# interface_dac_sma_feedback_2PS_ADC_detec.net
KiCad netlist of a schematic drawn in EAGLE
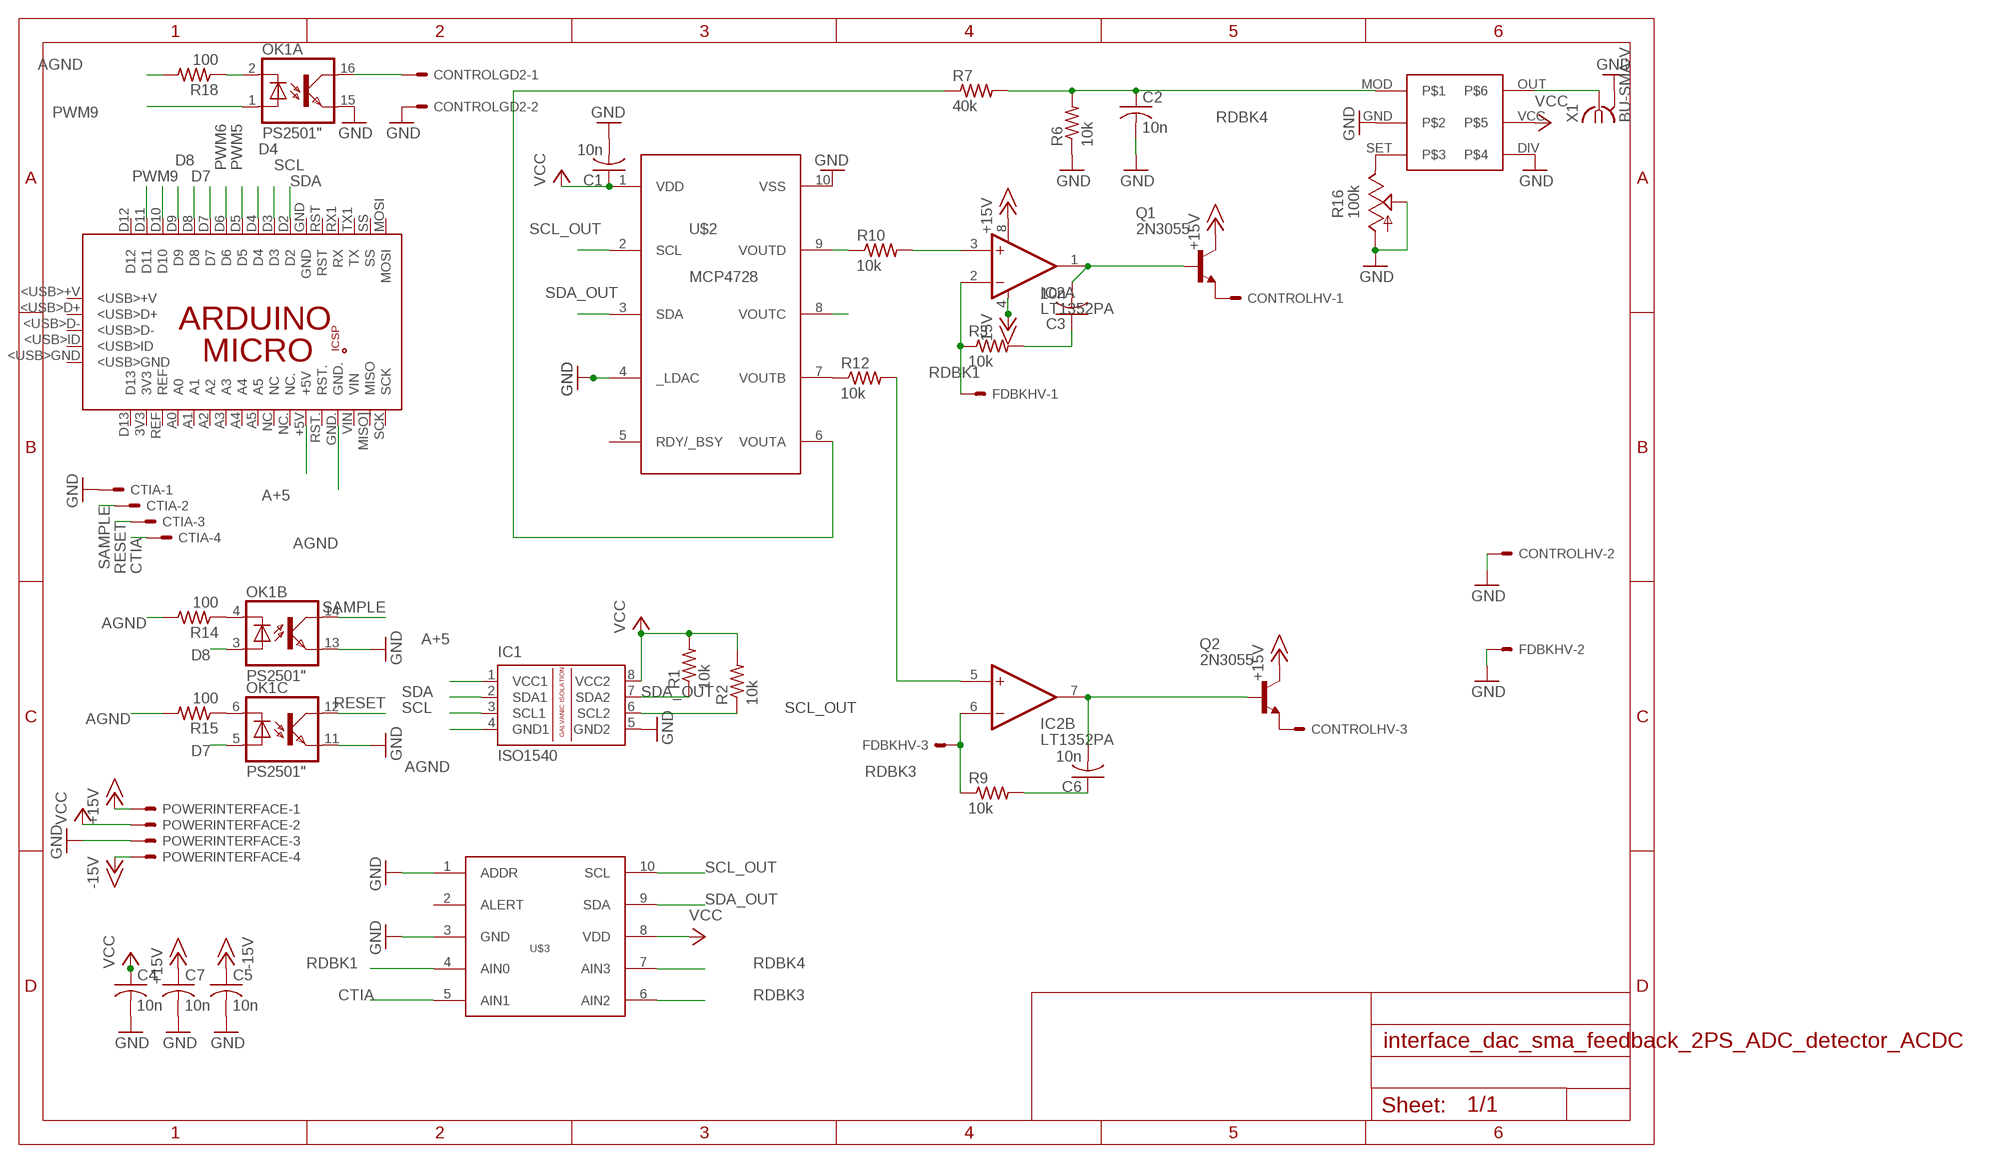
[diagram p0: schematic, sheet 1]

(export (version "E")
  (design (tool "Eeschema 10.0.6"))
  (components
    (comp (ref "C1")
      (value "10n")
      (footprint "eagle-import:C050-024X044")
      (libsource (lib "eagle-import") (part "C-US050-024X044"))
    )
    (comp (ref "C2")
      (value "10n")
      (footprint "eagle-import:C050-024X044")
      (libsource (lib "eagle-import") (part "resistor_C-US050-024X044"))
    )
    (comp (ref "C3")
      (value "10n")
      (footprint "eagle-import:C050-024X044")
      (libsource (lib "eagle-import") (part "resistor_C-US050-024X044"))
    )
    (comp (ref "C4")
      (value "10n")
      (footprint "eagle-import:C050-024X044")
      (libsource (lib "eagle-import") (part "resistor_C-US050-024X044"))
    )
    (comp (ref "C5")
      (value "10n")
      (footprint "eagle-import:C050-024X044")
      (libsource (lib "eagle-import") (part "resistor_C-US050-024X044"))
    )
    (comp (ref "C6")
      (value "10n")
      (footprint "eagle-import:C050-024X044")
      (libsource (lib "eagle-import") (part "resistor_C-US050-024X044"))
    )
    (comp (ref "C7")
      (value "10n")
      (footprint "eagle-import:C050-024X044")
      (libsource (lib "eagle-import") (part "resistor_C-US050-024X044"))
    )
    (comp (ref "CONTROLGD2")
      (value "KK-156-2")
      (footprint "eagle-import:KK-156-2")
      (libsource (lib "eagle-import") (part "KK-156-2"))
    )
    (comp (ref "CONTROLHV")
      (value "KK-156-3")
      (footprint "eagle-import:KK-156-3")
      (libsource (lib "eagle-import") (part "KK-156-3"))
    )
    (comp (ref "CTIA")
      (value "KK-156-4")
      (footprint "eagle-import:KK-156-4")
      (libsource (lib "eagle-import") (part "KK-156-4"))
    )
    (comp (ref "FDBKHV")
      (value "KK-156-3")
      (footprint "eagle-import:KK-156-3")
      (libsource (lib "eagle-import") (part "KK-156-3"))
    )
    (comp (ref "IC1")
      (value "ISO1540")
      (footprint "eagle-import:DIL08")
      (libsource (lib "eagle-import") (part "ISO1540"))
    )
    (comp (ref "IC2")
      (value "LT1352PA")
      (footprint "eagle-import:DIL08")
      (libsource (lib "eagle-import") (part "LT1352PA"))
    )
    (comp (ref "OK1")
      (value "PS2501\"")
      (footprint "eagle-import:DIL16")
      (libsource (lib "eagle-import") (part "PS2501{dblquote}"))
    )
    (comp (ref "PCB1")
      (value "ARDUINO_MICRO")
      (footprint "eagle-import:ARDUINO_MICRO")
      (libsource (lib "eagle-import") (part "ARDUINO_MICRO"))
    )
    (comp (ref "POWERINTERFACE")
      (value "KK-156-4")
      (footprint "eagle-import:KK-156-4")
      (libsource (lib "eagle-import") (part "KK-156-4"))
    )
    (comp (ref "Q1")
      (value "2N3055")
      (footprint "eagle-import:TO3")
      (libsource (lib "eagle-import") (part "2N3055"))
    )
    (comp (ref "Q2")
      (value "2N3055")
      (footprint "eagle-import:TO3")
      (libsource (lib "eagle-import") (part "2N3055"))
    )
    (comp (ref "R1")
      (value "10k")
      (footprint "eagle-import:0207_12")
      (libsource (lib "eagle-import") (part "resistor_R-US_0207/12"))
    )
    (comp (ref "R2")
      (value "10k")
      (footprint "eagle-import:0207_10")
      (libsource (lib "eagle-import") (part "resistor_R-US_0207/10"))
    )
    (comp (ref "R3")
      (value "10k")
      (footprint "eagle-import:0207_10")
      (libsource (lib "eagle-import") (part "resistor_R-US_0207/10"))
    )
    (comp (ref "R6")
      (value "10k")
      (footprint "eagle-import:0207_10")
      (libsource (lib "eagle-import") (part "resistor_R-US_0207/10"))
    )
    (comp (ref "R7")
      (value "40k")
      (footprint "eagle-import:0207_10")
      (libsource (lib "eagle-import") (part "resistor_R-US_0207/10"))
    )
    (comp (ref "R9")
      (value "10k")
      (footprint "eagle-import:0207_10")
      (libsource (lib "eagle-import") (part "resistor_R-US_0207/10"))
    )
    (comp (ref "R10")
      (value "10k")
      (footprint "eagle-import:0207_10")
      (libsource (lib "eagle-import") (part "resistor_R-US_0207/10"))
    )
    (comp (ref "R12")
      (value "10k")
      (footprint "eagle-import:0207_10")
      (libsource (lib "eagle-import") (part "resistor_R-US_0207/10"))
    )
    (comp (ref "R14")
      (value "100")
      (footprint "eagle-import:0207_10")
      (libsource (lib "eagle-import") (part "R-US_0207/10"))
    )
    (comp (ref "R15")
      (value "100")
      (footprint "eagle-import:0207_10")
      (libsource (lib "eagle-import") (part "R-US_0207/10"))
    )
    (comp (ref "R16")
      (value "100k")
      (footprint "eagle-import:SP19L")
      (libsource (lib "eagle-import") (part "TRIM_US-B90P"))
    )
    (comp (ref "R18")
      (value "100")
      (footprint "eagle-import:0207_10")
      (libsource (lib "eagle-import") (part "R-US_0207/10"))
    )
    (comp (ref "U$1")
      (value "LTC6992")
      (footprint "eagle-import:DIL06")
      (libsource (lib "eagle-import") (part "LTC6992"))
    )
    (comp (ref "U$2")
      (value "MCP4728DIL")
      (footprint "eagle-import:DIL10")
      (libsource (lib "eagle-import") (part "MCP4728DIL"))
    )
    (comp (ref "U$3")
      (value "ADS1015DIL")
      (footprint "eagle-import:DIL10")
      (libsource (lib "eagle-import") (part "ADS1015DIL"))
    )
    (comp (ref "X1")
      (value "BU-SMA-V")
      (footprint "eagle-import:BU-SMA-V")
      (libsource (lib "eagle-import") (part "BU-SMA-V"))
    )
  )
  (nets
    (net (code "1") (name "+15V") (class "Default")
      (node (ref "C7") (pin "1") (pinfunction "1_1") (pintype "passive"))
      (node (ref "IC2") (pin "8") (pinfunction "V+_8") (pintype "power_in"))
      (node (ref "POWERINTERFACE") (pin "1") (pinfunction "S_1") (pintype "passive"))
      (node (ref "Q1") (pin "C") (pinfunction "C_C") (pintype "passive"))
      (node (ref "Q1") (pin "C/") (pinfunction "C_C/") (pintype "passive"))
      (node (ref "Q2") (pin "C") (pinfunction "C_C") (pintype "passive"))
      (node (ref "Q2") (pin "C/") (pinfunction "C_C/") (pintype "passive"))
    )
    (net (code "2") (name "-15V") (class "Default")
      (node (ref "C5") (pin "1") (pinfunction "1_1") (pintype "passive"))
      (node (ref "IC2") (pin "4") (pinfunction "V-_4") (pintype "power_in"))
      (node (ref "POWERINTERFACE") (pin "4") (pinfunction "S_4") (pintype "passive"))
    )
    (net (code "3") (name "/A+5") (class "Default")
      (node (ref "IC1") (pin "1") (pinfunction "VCC1_1") (pintype "input"))
      (node (ref "PCB1") (pin "+5V") (pinfunction "+5V_+5V") (pintype "bidirectional"))
    )
    (net (code "4") (name "/AGND") (class "Default")
      (node (ref "IC1") (pin "4") (pinfunction "GND1_4") (pintype "input"))
      (node (ref "PCB1") (pin "GND.") (pinfunction "GND._GND.") (pintype "bidirectional"))
      (node (ref "R14") (pin "2") (pinfunction "2_2") (pintype "passive"))
      (node (ref "R15") (pin "2") (pinfunction "2_2") (pintype "passive"))
      (node (ref "R18") (pin "2") (pinfunction "2_2") (pintype "passive"))
    )
    (net (code "5") (name "/CTIA") (class "Default")
      (node (ref "CTIA") (pin "4") (pinfunction "S_4") (pintype "passive"))
      (node (ref "U$3") (pin "5") (pinfunction "AIN1_5") (pintype "bidirectional"))
    )
    (net (code "6") (name "/D4") (class "Default")
      (node (ref "PCB1") (pin "D4") (pinfunction "D4_D4") (pintype "bidirectional"))
    )
    (net (code "7") (name "/D7") (class "Default")
      (node (ref "OK1") (pin "5") (pinfunction "A_5") (pintype "passive"))
      (node (ref "PCB1") (pin "D7") (pinfunction "D7_D7") (pintype "bidirectional"))
    )
    (net (code "8") (name "/D8") (class "Default")
      (node (ref "OK1") (pin "3") (pinfunction "A_3") (pintype "passive"))
      (node (ref "PCB1") (pin "D8") (pinfunction "D8_D8") (pintype "bidirectional"))
    )
    (net (code "9") (name "/PWM5") (class "Default")
      (node (ref "PCB1") (pin "D5") (pinfunction "D5_D5") (pintype "bidirectional"))
    )
    (net (code "10") (name "/PWM6") (class "Default")
      (node (ref "PCB1") (pin "D6") (pinfunction "D6_D6") (pintype "bidirectional"))
    )
    (net (code "11") (name "/PWM9") (class "Default")
      (node (ref "OK1") (pin "1") (pinfunction "A_1") (pintype "passive"))
      (node (ref "PCB1") (pin "D9") (pinfunction "D9_D9") (pintype "bidirectional"))
    )
    (net (code "12") (name "/RDBK1") (class "Default")
      (node (ref "FDBKHV") (pin "1") (pinfunction "S_1") (pintype "passive"))
      (node (ref "IC2") (pin "2") (pinfunction "-IN_2") (pintype "input"))
      (node (ref "R3") (pin "1") (pinfunction "1_1") (pintype "passive"))
      (node (ref "U$3") (pin "4") (pinfunction "AIN0_4") (pintype "bidirectional"))
    )
    (net (code "13") (name "/RDBK3") (class "Default")
      (node (ref "FDBKHV") (pin "3") (pinfunction "S_3") (pintype "passive"))
      (node (ref "IC2") (pin "6") (pinfunction "-IN_6") (pintype "input"))
      (node (ref "R9") (pin "1") (pinfunction "1_1") (pintype "passive"))
      (node (ref "U$3") (pin "6") (pinfunction "AIN2_6") (pintype "bidirectional"))
    )
    (net (code "14") (name "/RDBK4") (class "Default")
      (node (ref "C2") (pin "1") (pinfunction "1_1") (pintype "passive"))
      (node (ref "R6") (pin "2") (pinfunction "2_2") (pintype "passive"))
      (node (ref "R7") (pin "2") (pinfunction "2_2") (pintype "passive"))
      (node (ref "U$1") (pin "MOD") (pinfunction "P$1_MOD") (pintype "bidirectional"))
      (node (ref "U$3") (pin "7") (pinfunction "AIN3_7") (pintype "bidirectional"))
    )
    (net (code "15") (name "/RESET") (class "Default")
      (node (ref "CTIA") (pin "3") (pinfunction "S_3") (pintype "passive"))
      (node (ref "OK1") (pin "12") (pinfunction "COL_12") (pintype "passive"))
    )
    (net (code "16") (name "/SAMPLE") (class "Default")
      (node (ref "CTIA") (pin "2") (pinfunction "S_2") (pintype "passive"))
      (node (ref "OK1") (pin "14") (pinfunction "COL_14") (pintype "passive"))
    )
    (net (code "17") (name "/SCL") (class "Default")
      (node (ref "IC1") (pin "3") (pinfunction "SCL1_3") (pintype "input"))
      (node (ref "PCB1") (pin "D3") (pinfunction "D3_D3") (pintype "bidirectional"))
    )
    (net (code "18") (name "/SCL_OUT") (class "Default")
      (node (ref "IC1") (pin "6") (pinfunction "SCL2_6") (pintype "input"))
      (node (ref "R2") (pin "1") (pinfunction "1_1") (pintype "passive"))
      (node (ref "U$2") (pin "2") (pinfunction "SCL_2") (pintype "bidirectional"))
      (node (ref "U$3") (pin "10") (pinfunction "SCL_10") (pintype "bidirectional"))
    )
    (net (code "19") (name "/SDA") (class "Default")
      (node (ref "IC1") (pin "2") (pinfunction "SDA1_2") (pintype "input"))
      (node (ref "PCB1") (pin "D2") (pinfunction "D2_D2") (pintype "bidirectional"))
    )
    (net (code "20") (name "/SDA_OUT") (class "Default")
      (node (ref "IC1") (pin "7") (pinfunction "SDA2_7") (pintype "input"))
      (node (ref "R1") (pin "1") (pinfunction "1_1") (pintype "passive"))
      (node (ref "U$2") (pin "3") (pinfunction "SDA_3") (pintype "bidirectional"))
      (node (ref "U$3") (pin "9") (pinfunction "SDA_9") (pintype "bidirectional"))
    )
    (net (code "21") (name "GND") (class "Default")
      (node (ref "C1") (pin "2") (pinfunction "2_2") (pintype "passive"))
      (node (ref "C2") (pin "2") (pinfunction "2_2") (pintype "passive"))
      (node (ref "C4") (pin "2") (pinfunction "2_2") (pintype "passive"))
      (node (ref "C5") (pin "2") (pinfunction "2_2") (pintype "passive"))
      (node (ref "C7") (pin "2") (pinfunction "2_2") (pintype "passive"))
      (node (ref "CONTROLGD2") (pin "2") (pinfunction "S_2") (pintype "passive"))
      (node (ref "CONTROLHV") (pin "2") (pinfunction "S_2") (pintype "passive"))
      (node (ref "CTIA") (pin "1") (pinfunction "S_1") (pintype "passive"))
      (node (ref "FDBKHV") (pin "2") (pinfunction "S_2") (pintype "passive"))
      (node (ref "IC1") (pin "5") (pinfunction "GND2_5") (pintype "input"))
      (node (ref "OK1") (pin "11") (pinfunction "EMI_11") (pintype "passive"))
      (node (ref "OK1") (pin "13") (pinfunction "EMI_13") (pintype "passive"))
      (node (ref "OK1") (pin "15") (pinfunction "EMI_15") (pintype "passive"))
      (node (ref "POWERINTERFACE") (pin "3") (pinfunction "S_3") (pintype "passive"))
      (node (ref "R16") (pin "A") (pinfunction "A_A") (pintype "passive"))
      (node (ref "R16") (pin "S") (pinfunction "S_S") (pintype "passive"))
      (node (ref "R6") (pin "1") (pinfunction "1_1") (pintype "passive"))
      (node (ref "U$1") (pin "DIV") (pinfunction "P$4_DIV") (pintype "bidirectional"))
      (node (ref "U$1") (pin "GND") (pinfunction "P$2_GND") (pintype "bidirectional"))
      (node (ref "U$2") (pin "10") (pinfunction "VSS_10") (pintype "bidirectional"))
      (node (ref "U$2") (pin "4") (pinfunction "_LDAC_4") (pintype "bidirectional"))
      (node (ref "U$3") (pin "1") (pinfunction "ADDR_1") (pintype "bidirectional"))
      (node (ref "U$3") (pin "3") (pinfunction "GND_3") (pintype "bidirectional"))
      (node (ref "X1") (pin "2") (pinfunction "2_2") (pintype "passive"))
      (node (ref "X1") (pin "3") (pinfunction "2_3") (pintype "passive"))
      (node (ref "X1") (pin "4") (pinfunction "2_4") (pintype "passive"))
      (node (ref "X1") (pin "5") (pinfunction "2_5") (pintype "passive"))
    )
    (net (code "22") (name "Net-(C3-Pad1)") (class "Default")
      (node (ref "C3") (pin "1") (pinfunction "1_1") (pintype "passive"))
      (node (ref "R3") (pin "2") (pinfunction "2_2") (pintype "passive"))
    )
    (net (code "23") (name "Net-(C6-Pad1)") (class "Default")
      (node (ref "C6") (pin "1") (pinfunction "1_1") (pintype "passive"))
      (node (ref "R9") (pin "2") (pinfunction "2_2") (pintype "passive"))
    )
    (net (code "24") (name "Net-(CONTROLGD2A-S)") (class "Default")
      (node (ref "CONTROLGD2") (pin "1") (pinfunction "S_1") (pintype "passive"))
      (node (ref "OK1") (pin "16") (pinfunction "COL_16") (pintype "passive"))
    )
    (net (code "25") (name "Net-(CONTROLHVA-S)") (class "Default")
      (node (ref "CONTROLHV") (pin "1") (pinfunction "S_1") (pintype "passive"))
      (node (ref "Q1") (pin "E") (pinfunction "E_E") (pintype "passive"))
    )
    (net (code "26") (name "Net-(CONTROLHVC-S)") (class "Default")
      (node (ref "CONTROLHV") (pin "3") (pinfunction "S_3") (pintype "passive"))
      (node (ref "Q2") (pin "E") (pinfunction "E_E") (pintype "passive"))
    )
    (net (code "27") (name "Net-(IC2A-+IN)") (class "Default")
      (node (ref "IC2") (pin "3") (pinfunction "+IN_3") (pintype "input"))
      (node (ref "R10") (pin "2") (pinfunction "2_2") (pintype "passive"))
    )
    (net (code "28") (name "Net-(IC2A-OUT)") (class "Default")
      (node (ref "C3") (pin "2") (pinfunction "2_2") (pintype "passive"))
      (node (ref "IC2") (pin "1") (pinfunction "OUT_1") (pintype "output"))
      (node (ref "Q1") (pin "B") (pinfunction "B_B") (pintype "passive"))
    )
    (net (code "29") (name "Net-(IC2B-+IN)") (class "Default")
      (node (ref "IC2") (pin "5") (pinfunction "+IN_5") (pintype "input"))
      (node (ref "R12") (pin "2") (pinfunction "2_2") (pintype "passive"))
    )
    (net (code "30") (name "Net-(IC2B-OUT)") (class "Default")
      (node (ref "C6") (pin "2") (pinfunction "2_2") (pintype "passive"))
      (node (ref "IC2") (pin "7") (pinfunction "OUT_7") (pintype "output"))
      (node (ref "Q2") (pin "B") (pinfunction "B_B") (pintype "passive"))
    )
    (net (code "31") (name "Net-(OK1A-C)") (class "Default")
      (node (ref "OK1") (pin "2") (pinfunction "C_2") (pintype "passive"))
      (node (ref "R18") (pin "1") (pinfunction "1_1") (pintype "passive"))
    )
    (net (code "32") (name "Net-(OK1B-C)") (class "Default")
      (node (ref "OK1") (pin "4") (pinfunction "C_4") (pintype "passive"))
      (node (ref "R14") (pin "1") (pinfunction "1_1") (pintype "passive"))
    )
    (net (code "33") (name "Net-(OK1C-C)") (class "Default")
      (node (ref "OK1") (pin "6") (pinfunction "C_6") (pintype "passive"))
      (node (ref "R15") (pin "1") (pinfunction "1_1") (pintype "passive"))
    )
    (net (code "34") (name "Net-(U$1-P$3)") (class "Default")
      (node (ref "R16") (pin "E") (pinfunction "E_E") (pintype "passive"))
      (node (ref "U$1") (pin "SET") (pinfunction "P$3_SET") (pintype "bidirectional"))
    )
    (net (code "35") (name "Net-(U$1-P$6)") (class "Default")
      (node (ref "U$1") (pin "OUT") (pinfunction "P$6_OUT") (pintype "bidirectional"))
      (node (ref "X1") (pin "1") (pinfunction "1_1") (pintype "passive"))
    )
    (net (code "36") (name "Net-(U$2-VOUTA)") (class "Default")
      (node (ref "R7") (pin "1") (pinfunction "1_1") (pintype "passive"))
      (node (ref "U$2") (pin "6") (pinfunction "VOUTA_6") (pintype "bidirectional"))
    )
    (net (code "37") (name "Net-(U$2-VOUTB)") (class "Default")
      (node (ref "R12") (pin "1") (pinfunction "1_1") (pintype "passive"))
      (node (ref "U$2") (pin "7") (pinfunction "VOUTB_7") (pintype "bidirectional"))
    )
    (net (code "38") (name "Net-(U$2-VOUTD)") (class "Default")
      (node (ref "R10") (pin "1") (pinfunction "1_1") (pintype "passive"))
      (node (ref "U$2") (pin "9") (pinfunction "VOUTD_9") (pintype "bidirectional"))
    )
    (net (code "39") (name "VCC") (class "Default")
      (node (ref "C1") (pin "1") (pinfunction "1_1") (pintype "passive"))
      (node (ref "C4") (pin "1") (pinfunction "1_1") (pintype "passive"))
      (node (ref "IC1") (pin "8") (pinfunction "VCC2_8") (pintype "input"))
      (node (ref "POWERINTERFACE") (pin "2") (pinfunction "S_2") (pintype "passive"))
      (node (ref "R1") (pin "2") (pinfunction "2_2") (pintype "passive"))
      (node (ref "R2") (pin "2") (pinfunction "2_2") (pintype "passive"))
      (node (ref "U$1") (pin "VCC") (pinfunction "P$5_VCC") (pintype "bidirectional"))
      (node (ref "U$2") (pin "1") (pinfunction "VDD_1") (pintype "bidirectional"))
      (node (ref "U$3") (pin "8") (pinfunction "VDD_8") (pintype "bidirectional"))
    )
    (net (code "40") (name "unconnected-(PCB1-MISO-PadMISO])") (class "Default")
      (node (ref "PCB1") (pin "MISO]") (pinfunction "MISO_MISO]") (pintype "bidirectional"))
    )
    (net (code "41") (name "unconnected-(PCB1-Pad3V3)") (class "Default")
      (node (ref "PCB1") (pin "3V3") (pinfunction "3V3_3V3") (pintype "bidirectional"))
    )
    (net (code "42") (name "unconnected-(PCB1-Pad5V)") (class "Default")
      (node (ref "PCB1") (pin "5V") (pinfunction "5V_5V") (pintype "bidirectional"))
    )
    (net (code "43") (name "unconnected-(PCB1-Pad<USB>+V)") (class "Default")
      (node (ref "PCB1") (pin "<USB>+V") (pinfunction "<USB>+V_<USB>+V") (pintype "bidirectional"))
    )
    (net (code "44") (name "unconnected-(PCB1-Pad<USB>D+)") (class "Default")
      (node (ref "PCB1") (pin "<USB>D+") (pinfunction "<USB>D+_<USB>D+") (pintype "bidirectional"))
    )
    (net (code "45") (name "unconnected-(PCB1-Pad<USB>D-)") (class "Default")
      (node (ref "PCB1") (pin "<USB>D-") (pinfunction "<USB>D-_<USB>D-") (pintype "bidirectional"))
    )
    (net (code "46") (name "unconnected-(PCB1-Pad<USB>GND)") (class "Default")
      (node (ref "PCB1") (pin "<USB>GND") (pinfunction "<USB>GND_<USB>GND") (pintype "bidirectional"))
    )
    (net (code "47") (name "unconnected-(PCB1-Pad<USB>ID)") (class "Default")
      (node (ref "PCB1") (pin "<USB>ID") (pinfunction "<USB>ID_<USB>ID") (pintype "bidirectional"))
    )
    (net (code "48") (name "unconnected-(PCB1-PadA0)") (class "Default")
      (node (ref "PCB1") (pin "A0") (pinfunction "A0_A0") (pintype "bidirectional"))
    )
    (net (code "49") (name "unconnected-(PCB1-PadA1)") (class "Default")
      (node (ref "PCB1") (pin "A1") (pinfunction "A1_A1") (pintype "bidirectional"))
    )
    (net (code "50") (name "unconnected-(PCB1-PadA2)") (class "Default")
      (node (ref "PCB1") (pin "A2") (pinfunction "A2_A2") (pintype "bidirectional"))
    )
    (net (code "51") (name "unconnected-(PCB1-PadA3)") (class "Default")
      (node (ref "PCB1") (pin "A3") (pinfunction "A3_A3") (pintype "bidirectional"))
    )
    (net (code "52") (name "unconnected-(PCB1-PadA4)") (class "Default")
      (node (ref "PCB1") (pin "A4") (pinfunction "A4_A4") (pintype "bidirectional"))
    )
    (net (code "53") (name "unconnected-(PCB1-PadA5)") (class "Default")
      (node (ref "PCB1") (pin "A5") (pinfunction "A5_A5") (pintype "bidirectional"))
    )
    (net (code "54") (name "unconnected-(PCB1-PadD10)") (class "Default")
      (node (ref "PCB1") (pin "D10") (pinfunction "D10_D10") (pintype "bidirectional"))
    )
    (net (code "55") (name "unconnected-(PCB1-PadD11)") (class "Default")
      (node (ref "PCB1") (pin "D11") (pinfunction "D11_D11") (pintype "bidirectional"))
    )
    (net (code "56") (name "unconnected-(PCB1-PadD12)") (class "Default")
      (node (ref "PCB1") (pin "D12") (pinfunction "D12_D12") (pintype "bidirectional"))
    )
    (net (code "57") (name "unconnected-(PCB1-PadD13)") (class "Default")
      (node (ref "PCB1") (pin "D13") (pinfunction "D13_D13") (pintype "bidirectional"))
    )
    (net (code "58") (name "unconnected-(PCB1-PadGND)") (class "Default")
      (node (ref "PCB1") (pin "GND") (pinfunction "GND_GND") (pintype "bidirectional"))
    )
    (net (code "59") (name "unconnected-(PCB1-PadGND_)") (class "Default")
      (node (ref "PCB1") (pin "GND_") (pinfunction "GND__GND_") (pintype "bidirectional"))
    )
    (net (code "60") (name "unconnected-(PCB1-PadMISO.)") (class "Default")
      (node (ref "PCB1") (pin "MISO.") (pinfunction "MISO._MISO.") (pintype "bidirectional"))
    )
    (net (code "61") (name "unconnected-(PCB1-PadMOSI)") (class "Default")
      (node (ref "PCB1") (pin "MOSI") (pinfunction "MOSI_MOSI") (pintype "bidirectional"))
    )
    (net (code "62") (name "unconnected-(PCB1-PadMOSI.)") (class "Default")
      (node (ref "PCB1") (pin "MOSI.") (pinfunction "MOSI._MOSI.") (pintype "bidirectional"))
    )
    (net (code "63") (name "unconnected-(PCB1-PadNC)") (class "Default")
      (node (ref "PCB1") (pin "NC") (pinfunction "NC_NC") (pintype "bidirectional"))
    )
    (net (code "64") (name "unconnected-(PCB1-PadNC.)") (class "Default")
      (node (ref "PCB1") (pin "NC.") (pinfunction "NC._NC.") (pintype "bidirectional"))
    )
    (net (code "65") (name "unconnected-(PCB1-PadREF)") (class "Default")
      (node (ref "PCB1") (pin "REF") (pinfunction "REF_REF") (pintype "bidirectional"))
    )
    (net (code "66") (name "unconnected-(PCB1-PadRESET..)") (class "Default")
      (node (ref "PCB1") (pin "RESET..") (pinfunction "RESET.._RESET..") (pintype "bidirectional"))
    )
    (net (code "67") (name "unconnected-(PCB1-PadRST)") (class "Default")
      (node (ref "PCB1") (pin "RST") (pinfunction "RST_RST") (pintype "bidirectional"))
    )
    (net (code "68") (name "unconnected-(PCB1-PadRST.)") (class "Default")
      (node (ref "PCB1") (pin "RST.") (pinfunction "RST._RST.") (pintype "bidirectional"))
    )
    (net (code "69") (name "unconnected-(PCB1-PadSCK)") (class "Default")
      (node (ref "PCB1") (pin "SCK") (pinfunction "SCK_SCK") (pintype "bidirectional"))
    )
    (net (code "70") (name "unconnected-(PCB1-PadSCK.)") (class "Default")
      (node (ref "PCB1") (pin "SCK.") (pinfunction "SCK._SCK.") (pintype "bidirectional"))
    )
    (net (code "71") (name "unconnected-(PCB1-PadSS)") (class "Default")
      (node (ref "PCB1") (pin "SS") (pinfunction "SS_SS") (pintype "bidirectional"))
    )
    (net (code "72") (name "unconnected-(PCB1-PadVIN)") (class "Default")
      (node (ref "PCB1") (pin "VIN") (pinfunction "VIN_VIN") (pintype "bidirectional"))
    )
    (net (code "73") (name "unconnected-(PCB1-RX-PadRX1)") (class "Default")
      (node (ref "PCB1") (pin "RX1") (pinfunction "RX_RX1") (pintype "bidirectional"))
    )
    (net (code "74") (name "unconnected-(PCB1-TX-PadTX1)") (class "Default")
      (node (ref "PCB1") (pin "TX1") (pinfunction "TX_TX1") (pintype "bidirectional"))
    )
    (net (code "75") (name "unconnected-(U$2-RDY{slash}_BSY-Pad5)") (class "Default")
      (node (ref "U$2") (pin "5") (pinfunction "RDY/_BSY_5") (pintype "bidirectional"))
    )
    (net (code "76") (name "unconnected-(U$2-VOUTC-Pad8)") (class "Default")
      (node (ref "U$2") (pin "8") (pinfunction "VOUTC_8") (pintype "bidirectional"))
    )
    (net (code "77") (name "unconnected-(U$3-ALERT-Pad2)") (class "Default")
      (node (ref "U$3") (pin "2") (pinfunction "ALERT_2") (pintype "bidirectional"))
    )
  )
)
